# Output_v2_1.net
KiCad netlist of a schematic drawn in EAGLE
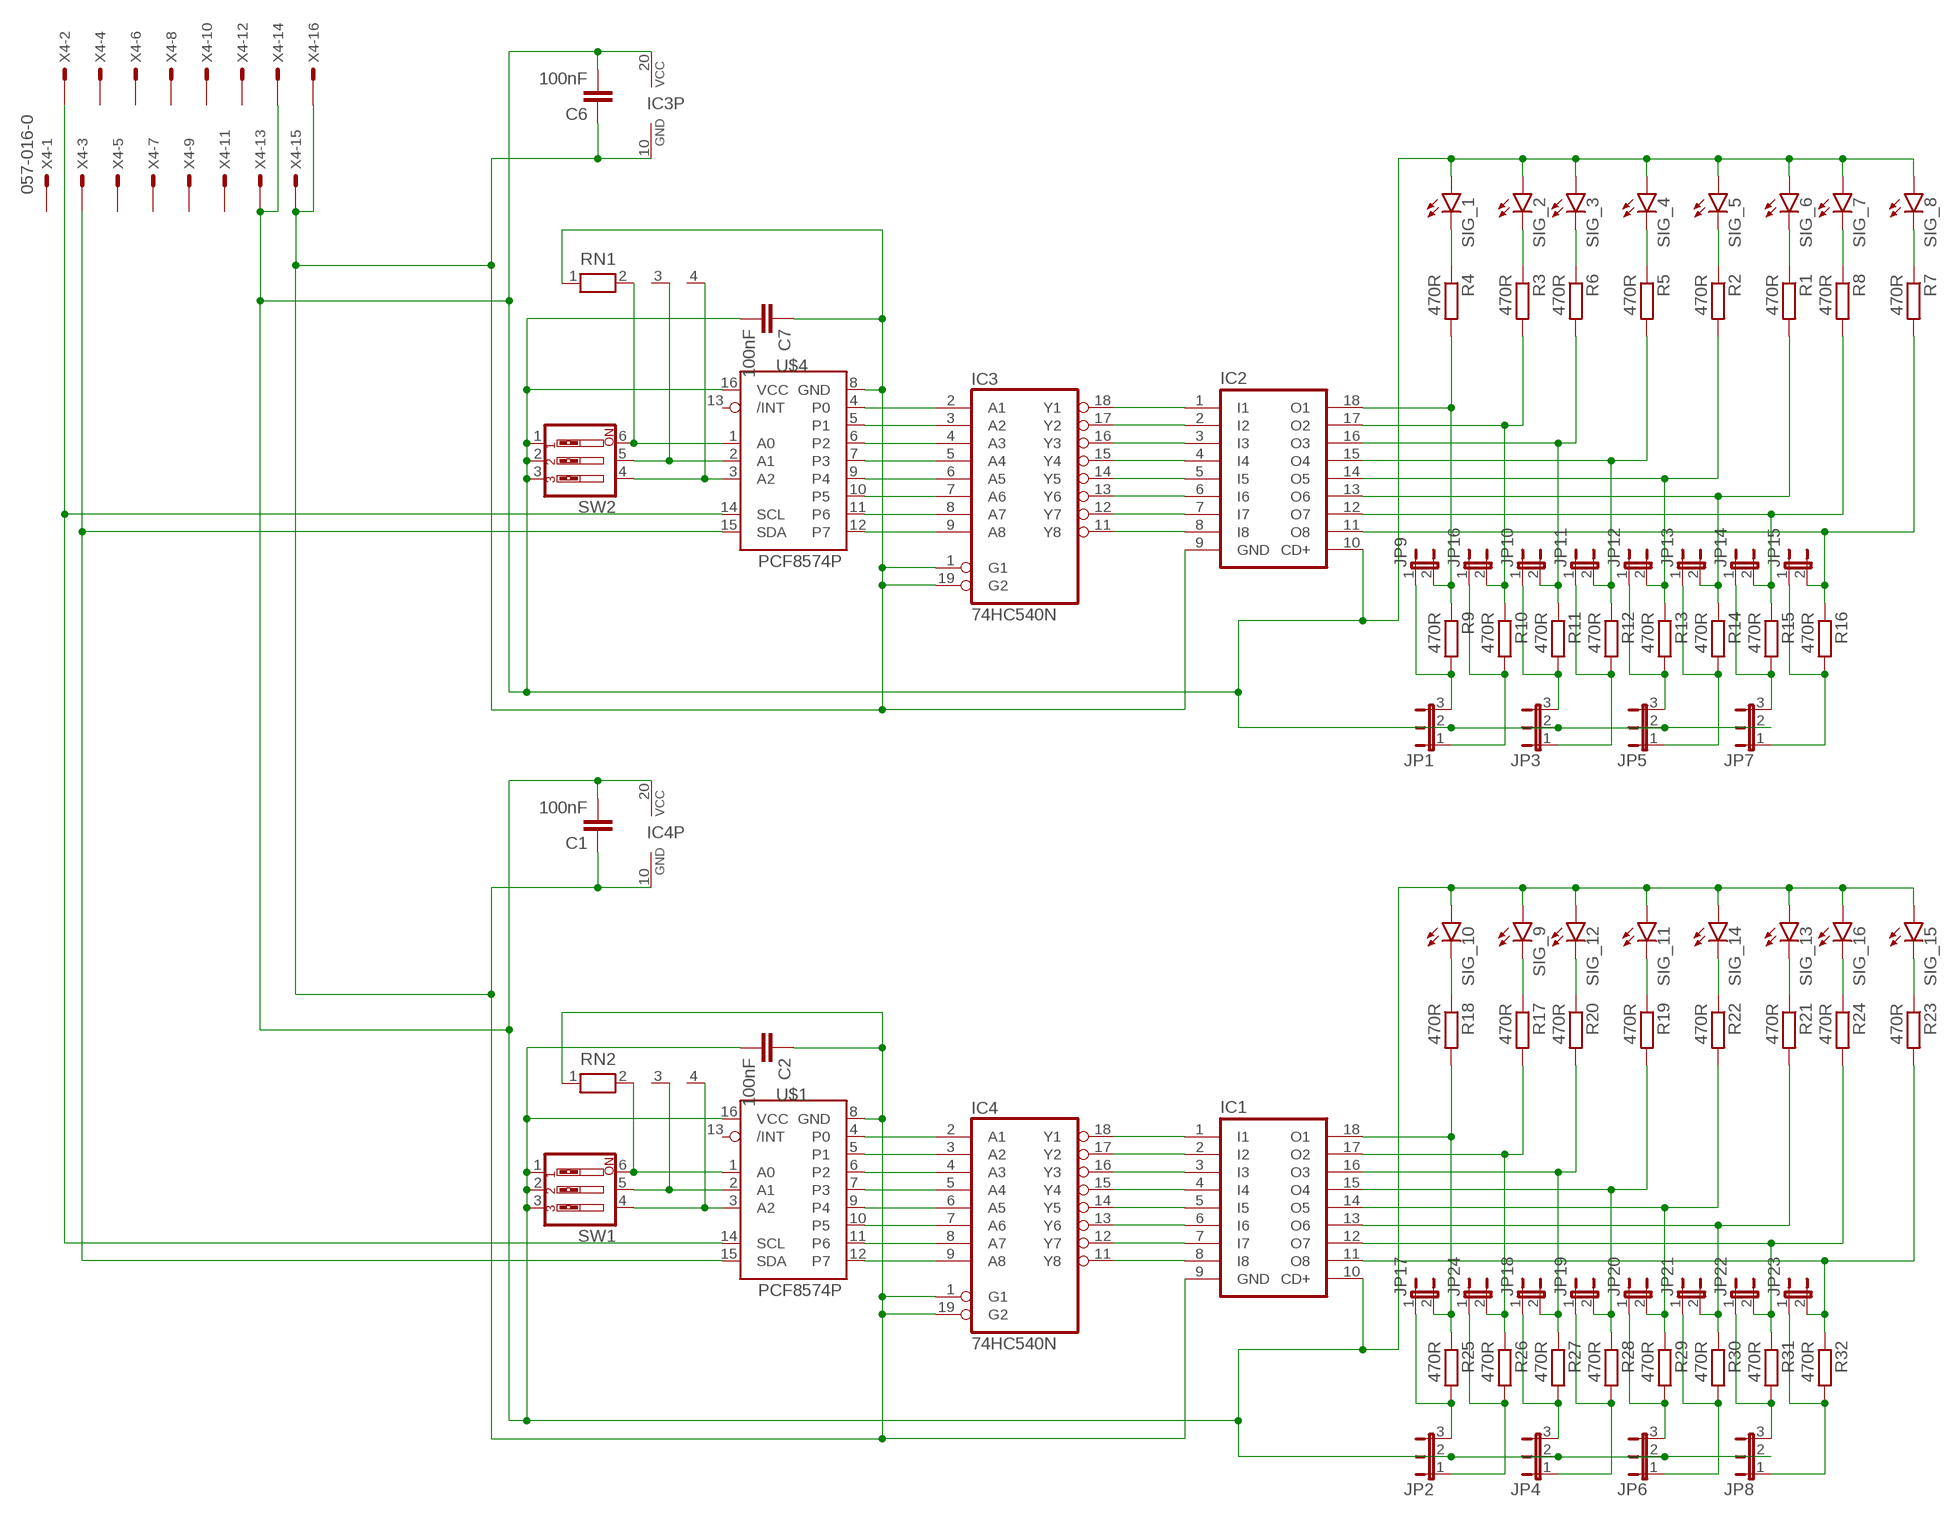
[diagram p0: schematic, sheet 1]

(export (version "E")
  (design (tool "Eeschema 10.0.6"))
  (components
    (comp (ref "C1")
      (value "100nF")
      (footprint "eagle-import:C025-024X044")
      (libsource (lib "eagle-import") (part "C-EU025-024X044"))
    )
    (comp (ref "C2")
      (value "100nF")
      (footprint "eagle-import:C025-024X044")
      (libsource (lib "eagle-import") (part "C-EU025-024X044"))
    )
    (comp (ref "C6")
      (value "100nF")
      (footprint "eagle-import:C025-024X044")
      (libsource (lib "eagle-import") (part "C-EU025-024X044"))
    )
    (comp (ref "C7")
      (value "100nF")
      (footprint "eagle-import:C025-024X044")
      (libsource (lib "eagle-import") (part "C-EU025-024X044"))
    )
    (comp (ref "IC1")
      (value "ULN2803A")
      (footprint "eagle-import:DIL18")
      (libsource (lib "eagle-import") (part "ULN2803A"))
    )
    (comp (ref "IC2")
      (value "ULN2803A")
      (footprint "eagle-import:DIL18")
      (libsource (lib "eagle-import") (part "ULN2803A"))
    )
    (comp (ref "IC3")
      (value "74HC540N")
      (footprint "eagle-import:DIL20")
      (libsource (lib "eagle-import") (part "74540NHC"))
    )
    (comp (ref "IC4")
      (value "74HC540N")
      (footprint "eagle-import:DIL20")
      (libsource (lib "eagle-import") (part "74540NHC"))
    )
    (comp (ref "JP1")
      (value "JP2E")
      (footprint "eagle-import:JP2")
      (libsource (lib "eagle-import") (part "JP2E"))
    )
    (comp (ref "JP2")
      (value "JP2E")
      (footprint "eagle-import:JP2")
      (libsource (lib "eagle-import") (part "JP2E"))
    )
    (comp (ref "JP3")
      (value "JP2E")
      (footprint "eagle-import:JP2")
      (libsource (lib "eagle-import") (part "JP2E"))
    )
    (comp (ref "JP4")
      (value "JP2E")
      (footprint "eagle-import:JP2")
      (libsource (lib "eagle-import") (part "JP2E"))
    )
    (comp (ref "JP5")
      (value "JP2E")
      (footprint "eagle-import:JP2")
      (libsource (lib "eagle-import") (part "JP2E"))
    )
    (comp (ref "JP6")
      (value "JP2E")
      (footprint "eagle-import:JP2")
      (libsource (lib "eagle-import") (part "JP2E"))
    )
    (comp (ref "JP7")
      (value "JP2E")
      (footprint "eagle-import:JP2")
      (libsource (lib "eagle-import") (part "JP2E"))
    )
    (comp (ref "JP8")
      (value "JP2E")
      (footprint "eagle-import:JP2")
      (libsource (lib "eagle-import") (part "JP2E"))
    )
    (comp (ref "JP9")
      (value "JP1E")
      (footprint "eagle-import:JP1")
      (libsource (lib "eagle-import") (part "JP1E"))
    )
    (comp (ref "JP10")
      (value "JP1E")
      (footprint "eagle-import:JP1")
      (libsource (lib "eagle-import") (part "JP1E"))
    )
    (comp (ref "JP11")
      (value "JP1E")
      (footprint "eagle-import:JP1")
      (libsource (lib "eagle-import") (part "JP1E"))
    )
    (comp (ref "JP12")
      (value "JP1E")
      (footprint "eagle-import:JP1")
      (libsource (lib "eagle-import") (part "JP1E"))
    )
    (comp (ref "JP13")
      (value "JP1E")
      (footprint "eagle-import:JP1")
      (libsource (lib "eagle-import") (part "JP1E"))
    )
    (comp (ref "JP14")
      (value "JP1E")
      (footprint "eagle-import:JP1")
      (libsource (lib "eagle-import") (part "JP1E"))
    )
    (comp (ref "JP15")
      (value "JP1E")
      (footprint "eagle-import:JP1")
      (libsource (lib "eagle-import") (part "JP1E"))
    )
    (comp (ref "JP16")
      (value "JP1E")
      (footprint "eagle-import:JP1")
      (libsource (lib "eagle-import") (part "JP1E"))
    )
    (comp (ref "JP17")
      (value "JP1E")
      (footprint "eagle-import:JP1")
      (libsource (lib "eagle-import") (part "JP1E"))
    )
    (comp (ref "JP18")
      (value "JP1E")
      (footprint "eagle-import:JP1")
      (libsource (lib "eagle-import") (part "JP1E"))
    )
    (comp (ref "JP19")
      (value "JP1E")
      (footprint "eagle-import:JP1")
      (libsource (lib "eagle-import") (part "JP1E"))
    )
    (comp (ref "JP20")
      (value "JP1E")
      (footprint "eagle-import:JP1")
      (libsource (lib "eagle-import") (part "JP1E"))
    )
    (comp (ref "JP21")
      (value "JP1E")
      (footprint "eagle-import:JP1")
      (libsource (lib "eagle-import") (part "JP1E"))
    )
    (comp (ref "JP22")
      (value "JP1E")
      (footprint "eagle-import:JP1")
      (libsource (lib "eagle-import") (part "JP1E"))
    )
    (comp (ref "JP23")
      (value "JP1E")
      (footprint "eagle-import:JP1")
      (libsource (lib "eagle-import") (part "JP1E"))
    )
    (comp (ref "JP24")
      (value "JP1E")
      (footprint "eagle-import:JP1")
      (libsource (lib "eagle-import") (part "JP1E"))
    )
    (comp (ref "R1")
      (value "470R")
      (footprint "eagle-import:0309_10")
      (libsource (lib "eagle-import") (part "R-EU_0309/10"))
    )
    (comp (ref "R2")
      (value "470R")
      (footprint "eagle-import:0309_10")
      (libsource (lib "eagle-import") (part "R-EU_0309/10"))
    )
    (comp (ref "R3")
      (value "470R")
      (footprint "eagle-import:0309_10")
      (libsource (lib "eagle-import") (part "R-EU_0309/10"))
    )
    (comp (ref "R4")
      (value "470R")
      (footprint "eagle-import:0309_10")
      (libsource (lib "eagle-import") (part "R-EU_0309/10"))
    )
    (comp (ref "R5")
      (value "470R")
      (footprint "eagle-import:0309_10")
      (libsource (lib "eagle-import") (part "R-EU_0309/10"))
    )
    (comp (ref "R6")
      (value "470R")
      (footprint "eagle-import:0309_10")
      (libsource (lib "eagle-import") (part "R-EU_0309/10"))
    )
    (comp (ref "R7")
      (value "470R")
      (footprint "eagle-import:0309_10")
      (libsource (lib "eagle-import") (part "R-EU_0309/10"))
    )
    (comp (ref "R8")
      (value "470R")
      (footprint "eagle-import:0309_10")
      (libsource (lib "eagle-import") (part "R-EU_0309/10"))
    )
    (comp (ref "R9")
      (value "470R")
      (footprint "eagle-import:0309_10")
      (libsource (lib "eagle-import") (part "R-EU_0309/10"))
    )
    (comp (ref "R10")
      (value "470R")
      (footprint "eagle-import:0309_10")
      (libsource (lib "eagle-import") (part "R-EU_0309/10"))
    )
    (comp (ref "R11")
      (value "470R")
      (footprint "eagle-import:0309_10")
      (libsource (lib "eagle-import") (part "R-EU_0309/10"))
    )
    (comp (ref "R12")
      (value "470R")
      (footprint "eagle-import:0309_10")
      (libsource (lib "eagle-import") (part "R-EU_0309/10"))
    )
    (comp (ref "R13")
      (value "470R")
      (footprint "eagle-import:0309_10")
      (libsource (lib "eagle-import") (part "R-EU_0309/10"))
    )
    (comp (ref "R14")
      (value "470R")
      (footprint "eagle-import:0309_10")
      (libsource (lib "eagle-import") (part "R-EU_0309/10"))
    )
    (comp (ref "R15")
      (value "470R")
      (footprint "eagle-import:0309_10")
      (libsource (lib "eagle-import") (part "R-EU_0309/10"))
    )
    (comp (ref "R16")
      (value "470R")
      (footprint "eagle-import:0309_10")
      (libsource (lib "eagle-import") (part "R-EU_0309/10"))
    )
    (comp (ref "R17")
      (value "470R")
      (footprint "eagle-import:0309_10")
      (libsource (lib "eagle-import") (part "R-EU_0309/10"))
    )
    (comp (ref "R18")
      (value "470R")
      (footprint "eagle-import:0309_10")
      (libsource (lib "eagle-import") (part "R-EU_0309/10"))
    )
    (comp (ref "R19")
      (value "470R")
      (footprint "eagle-import:0309_10")
      (libsource (lib "eagle-import") (part "R-EU_0309/10"))
    )
    (comp (ref "R20")
      (value "470R")
      (footprint "eagle-import:0309_10")
      (libsource (lib "eagle-import") (part "R-EU_0309/10"))
    )
    (comp (ref "R21")
      (value "470R")
      (footprint "eagle-import:0309_10")
      (libsource (lib "eagle-import") (part "R-EU_0309/10"))
    )
    (comp (ref "R22")
      (value "470R")
      (footprint "eagle-import:0309_10")
      (libsource (lib "eagle-import") (part "R-EU_0309/10"))
    )
    (comp (ref "R23")
      (value "470R")
      (footprint "eagle-import:0309_10")
      (libsource (lib "eagle-import") (part "R-EU_0309/10"))
    )
    (comp (ref "R24")
      (value "470R")
      (footprint "eagle-import:0309_10")
      (libsource (lib "eagle-import") (part "R-EU_0309/10"))
    )
    (comp (ref "R25")
      (value "470R")
      (footprint "eagle-import:0309_10")
      (libsource (lib "eagle-import") (part "R-EU_0309/10"))
    )
    (comp (ref "R26")
      (value "470R")
      (footprint "eagle-import:0309_10")
      (libsource (lib "eagle-import") (part "R-EU_0309/10"))
    )
    (comp (ref "R27")
      (value "470R")
      (footprint "eagle-import:0309_10")
      (libsource (lib "eagle-import") (part "R-EU_0309/10"))
    )
    (comp (ref "R28")
      (value "470R")
      (footprint "eagle-import:0309_10")
      (libsource (lib "eagle-import") (part "R-EU_0309/10"))
    )
    (comp (ref "R29")
      (value "470R")
      (footprint "eagle-import:0309_10")
      (libsource (lib "eagle-import") (part "R-EU_0309/10"))
    )
    (comp (ref "R30")
      (value "470R")
      (footprint "eagle-import:0309_10")
      (libsource (lib "eagle-import") (part "R-EU_0309/10"))
    )
    (comp (ref "R31")
      (value "470R")
      (footprint "eagle-import:0309_10")
      (libsource (lib "eagle-import") (part "R-EU_0309/10"))
    )
    (comp (ref "R32")
      (value "470R")
      (footprint "eagle-import:0309_10")
      (libsource (lib "eagle-import") (part "R-EU_0309/10"))
    )
    (comp (ref "RN1")
      (value "RN03")
      (footprint "eagle-import:RN-3")
      (libsource (lib "eagle-import") (part "RN03"))
    )
    (comp (ref "RN2")
      (value "RN03")
      (footprint "eagle-import:RN-3")
      (libsource (lib "eagle-import") (part "RN03"))
    )
    (comp (ref "SIG_1")
      (value "LED3MM")
      (footprint "eagle-import:LED3MM")
      (libsource (lib "eagle-import") (part "LED3MM"))
    )
    (comp (ref "SIG_2")
      (value "LED3MM")
      (footprint "eagle-import:LED3MM")
      (libsource (lib "eagle-import") (part "LED3MM"))
    )
    (comp (ref "SIG_3")
      (value "LED3MM")
      (footprint "eagle-import:LED3MM")
      (libsource (lib "eagle-import") (part "LED3MM"))
    )
    (comp (ref "SIG_4")
      (value "LED3MM")
      (footprint "eagle-import:LED3MM")
      (libsource (lib "eagle-import") (part "LED3MM"))
    )
    (comp (ref "SIG_5")
      (value "LED3MM")
      (footprint "eagle-import:LED3MM")
      (libsource (lib "eagle-import") (part "LED3MM"))
    )
    (comp (ref "SIG_6")
      (value "LED3MM")
      (footprint "eagle-import:LED3MM")
      (libsource (lib "eagle-import") (part "LED3MM"))
    )
    (comp (ref "SIG_7")
      (value "LED3MM")
      (footprint "eagle-import:LED3MM")
      (libsource (lib "eagle-import") (part "LED3MM"))
    )
    (comp (ref "SIG_8")
      (value "LED3MM")
      (footprint "eagle-import:LED3MM")
      (libsource (lib "eagle-import") (part "LED3MM"))
    )
    (comp (ref "SIG_9")
      (value "LED3MM")
      (footprint "eagle-import:LED3MM")
      (libsource (lib "eagle-import") (part "LED3MM"))
    )
    (comp (ref "SIG_10")
      (value "LED3MM")
      (footprint "eagle-import:LED3MM")
      (libsource (lib "eagle-import") (part "LED3MM"))
    )
    (comp (ref "SIG_11")
      (value "LED3MM")
      (footprint "eagle-import:LED3MM")
      (libsource (lib "eagle-import") (part "LED3MM"))
    )
    (comp (ref "SIG_12")
      (value "LED3MM")
      (footprint "eagle-import:LED3MM")
      (libsource (lib "eagle-import") (part "LED3MM"))
    )
    (comp (ref "SIG_13")
      (value "LED3MM")
      (footprint "eagle-import:LED3MM")
      (libsource (lib "eagle-import") (part "LED3MM"))
    )
    (comp (ref "SIG_14")
      (value "LED3MM")
      (footprint "eagle-import:LED3MM")
      (libsource (lib "eagle-import") (part "LED3MM"))
    )
    (comp (ref "SIG_15")
      (value "LED3MM")
      (footprint "eagle-import:LED3MM")
      (libsource (lib "eagle-import") (part "LED3MM"))
    )
    (comp (ref "SIG_16")
      (value "LED3MM")
      (footprint "eagle-import:LED3MM")
      (libsource (lib "eagle-import") (part "LED3MM"))
    )
    (comp (ref "SW1")
      (value "SW_DIP-3")
      (footprint "eagle-import:EDG-03")
      (libsource (lib "eagle-import") (part "SW_DIP-3"))
    )
    (comp (ref "SW2")
      (value "SW_DIP-3")
      (footprint "eagle-import:EDG-03")
      (libsource (lib "eagle-import") (part "SW_DIP-3"))
    )
    (comp (ref "U$1")
      (value "PCF8574P")
      (footprint "eagle-import:DIL16")
      (libsource (lib "eagle-import") (part "PCF8574P"))
    )
    (comp (ref "U$4")
      (value "PCF8574P")
      (footprint "eagle-import:DIL16")
      (libsource (lib "eagle-import") (part "PCF8574P"))
    )
    (comp (ref "X4")
      (value "057-016-0")
      (footprint "eagle-import:057-016-0")
      (libsource (lib "eagle-import") (part "057-016-0"))
    )
  )
  (nets
    (net (code "1") (name "Net-(IC1-CD+)") (class "Default")
      (node (ref "C1") (pin "2") (pinfunction "2_2") (pintype "passive"))
      (node (ref "C2") (pin "2") (pinfunction "2_2") (pintype "passive"))
      (node (ref "C6") (pin "2") (pinfunction "2_2") (pintype "passive"))
      (node (ref "C7") (pin "2") (pinfunction "2_2") (pintype "passive"))
      (node (ref "IC1") (pin "10") (pinfunction "CD+_10") (pintype "passive"))
      (node (ref "IC2") (pin "10") (pinfunction "CD+_10") (pintype "passive"))
      (node (ref "IC3") (pin "20") (pinfunction "VCC_20") (pintype "power_in"))
      (node (ref "IC4") (pin "20") (pinfunction "VCC_20") (pintype "power_in"))
      (node (ref "JP1") (pin "2") (pinfunction "2_2") (pintype "passive"))
      (node (ref "JP2") (pin "2") (pinfunction "2_2") (pintype "passive"))
      (node (ref "JP3") (pin "2") (pinfunction "2_2") (pintype "passive"))
      (node (ref "JP4") (pin "2") (pinfunction "2_2") (pintype "passive"))
      (node (ref "JP5") (pin "2") (pinfunction "2_2") (pintype "passive"))
      (node (ref "JP6") (pin "2") (pinfunction "2_2") (pintype "passive"))
      (node (ref "JP7") (pin "2") (pinfunction "2_2") (pintype "passive"))
      (node (ref "JP8") (pin "2") (pinfunction "2_2") (pintype "passive"))
      (node (ref "SIG_1") (pin "A") (pinfunction "A_A") (pintype "passive"))
      (node (ref "SIG_10") (pin "A") (pinfunction "A_A") (pintype "passive"))
      (node (ref "SIG_11") (pin "A") (pinfunction "A_A") (pintype "passive"))
      (node (ref "SIG_12") (pin "A") (pinfunction "A_A") (pintype "passive"))
      (node (ref "SIG_13") (pin "A") (pinfunction "A_A") (pintype "passive"))
      (node (ref "SIG_14") (pin "A") (pinfunction "A_A") (pintype "passive"))
      (node (ref "SIG_15") (pin "A") (pinfunction "A_A") (pintype "passive"))
      (node (ref "SIG_16") (pin "A") (pinfunction "A_A") (pintype "passive"))
      (node (ref "SIG_2") (pin "A") (pinfunction "A_A") (pintype "passive"))
      (node (ref "SIG_3") (pin "A") (pinfunction "A_A") (pintype "passive"))
      (node (ref "SIG_4") (pin "A") (pinfunction "A_A") (pintype "passive"))
      (node (ref "SIG_5") (pin "A") (pinfunction "A_A") (pintype "passive"))
      (node (ref "SIG_6") (pin "A") (pinfunction "A_A") (pintype "passive"))
      (node (ref "SIG_7") (pin "A") (pinfunction "A_A") (pintype "passive"))
      (node (ref "SIG_8") (pin "A") (pinfunction "A_A") (pintype "passive"))
      (node (ref "SIG_9") (pin "A") (pinfunction "A_A") (pintype "passive"))
      (node (ref "SW1") (pin "1") (pinfunction "1_1") (pintype "passive"))
      (node (ref "SW1") (pin "2") (pinfunction "2_2") (pintype "passive"))
      (node (ref "SW1") (pin "3") (pinfunction "3_3") (pintype "passive"))
      (node (ref "SW2") (pin "1") (pinfunction "1_1") (pintype "passive"))
      (node (ref "SW2") (pin "2") (pinfunction "2_2") (pintype "passive"))
      (node (ref "SW2") (pin "3") (pinfunction "3_3") (pintype "passive"))
      (node (ref "U$1") (pin "16") (pinfunction "VCC_16") (pintype "power_in"))
      (node (ref "U$4") (pin "16") (pinfunction "VCC_16") (pintype "power_in"))
      (node (ref "X4") (pin "13") (pinfunction "S_13") (pintype "passive"))
      (node (ref "X4") (pin "14") (pinfunction "S_14") (pintype "passive"))
    )
    (net (code "2") (name "Net-(IC1-GND)") (class "Default")
      (node (ref "C1") (pin "1") (pinfunction "1_1") (pintype "passive"))
      (node (ref "C2") (pin "1") (pinfunction "1_1") (pintype "passive"))
      (node (ref "C6") (pin "1") (pinfunction "1_1") (pintype "passive"))
      (node (ref "C7") (pin "1") (pinfunction "1_1") (pintype "passive"))
      (node (ref "IC1") (pin "9") (pinfunction "GND_9") (pintype "power_in"))
      (node (ref "IC2") (pin "9") (pinfunction "GND_9") (pintype "power_in"))
      (node (ref "IC3") (pin "1") (pinfunction "G1_1") (pintype "input"))
      (node (ref "IC3") (pin "10") (pinfunction "GND_10") (pintype "power_in"))
      (node (ref "IC3") (pin "19") (pinfunction "G2_19") (pintype "input"))
      (node (ref "IC4") (pin "1") (pinfunction "G1_1") (pintype "input"))
      (node (ref "IC4") (pin "10") (pinfunction "GND_10") (pintype "power_in"))
      (node (ref "IC4") (pin "19") (pinfunction "G2_19") (pintype "input"))
      (node (ref "RN1") (pin "1") (pinfunction "1_1") (pintype "passive"))
      (node (ref "RN2") (pin "1") (pinfunction "1_1") (pintype "passive"))
      (node (ref "U$1") (pin "8") (pinfunction "GND_8") (pintype "power_in"))
      (node (ref "U$4") (pin "8") (pinfunction "GND_8") (pintype "power_in"))
      (node (ref "X4") (pin "15") (pinfunction "S_15") (pintype "passive"))
      (node (ref "X4") (pin "16") (pinfunction "S_16") (pintype "passive"))
    )
    (net (code "3") (name "Net-(IC1-I1)") (class "Default")
      (node (ref "IC1") (pin "1") (pinfunction "I1_1") (pintype "input"))
      (node (ref "IC4") (pin "18") (pinfunction "Y1_18") (pintype "tri_state"))
    )
    (net (code "4") (name "Net-(IC1-I2)") (class "Default")
      (node (ref "IC1") (pin "2") (pinfunction "I2_2") (pintype "input"))
      (node (ref "IC4") (pin "17") (pinfunction "Y2_17") (pintype "tri_state"))
    )
    (net (code "5") (name "Net-(IC1-I3)") (class "Default")
      (node (ref "IC1") (pin "3") (pinfunction "I3_3") (pintype "input"))
      (node (ref "IC4") (pin "16") (pinfunction "Y3_16") (pintype "tri_state"))
    )
    (net (code "6") (name "Net-(IC1-I4)") (class "Default")
      (node (ref "IC1") (pin "4") (pinfunction "I4_4") (pintype "input"))
      (node (ref "IC4") (pin "15") (pinfunction "Y4_15") (pintype "tri_state"))
    )
    (net (code "7") (name "Net-(IC1-I5)") (class "Default")
      (node (ref "IC1") (pin "5") (pinfunction "I5_5") (pintype "input"))
      (node (ref "IC4") (pin "14") (pinfunction "Y5_14") (pintype "tri_state"))
    )
    (net (code "8") (name "Net-(IC1-I6)") (class "Default")
      (node (ref "IC1") (pin "6") (pinfunction "I6_6") (pintype "input"))
      (node (ref "IC4") (pin "13") (pinfunction "Y6_13") (pintype "tri_state"))
    )
    (net (code "9") (name "Net-(IC1-I7)") (class "Default")
      (node (ref "IC1") (pin "7") (pinfunction "I7_7") (pintype "input"))
      (node (ref "IC4") (pin "12") (pinfunction "Y7_12") (pintype "tri_state"))
    )
    (net (code "10") (name "Net-(IC1-I8)") (class "Default")
      (node (ref "IC1") (pin "8") (pinfunction "I8_8") (pintype "input"))
      (node (ref "IC4") (pin "11") (pinfunction "Y8_11") (pintype "tri_state"))
    )
    (net (code "11") (name "Net-(IC1-O1)") (class "Default")
      (node (ref "IC1") (pin "18") (pinfunction "O1_18") (pintype "open_collector"))
      (node (ref "JP17") (pin "2") (pinfunction "2_2") (pintype "passive"))
      (node (ref "R18") (pin "2") (pinfunction "2_2") (pintype "passive"))
      (node (ref "R25") (pin "1") (pinfunction "1_1") (pintype "passive"))
    )
    (net (code "12") (name "Net-(IC1-O2)") (class "Default")
      (node (ref "IC1") (pin "17") (pinfunction "O2_17") (pintype "open_collector"))
      (node (ref "JP24") (pin "2") (pinfunction "2_2") (pintype "passive"))
      (node (ref "R17") (pin "2") (pinfunction "2_2") (pintype "passive"))
      (node (ref "R26") (pin "1") (pinfunction "1_1") (pintype "passive"))
    )
    (net (code "13") (name "Net-(IC1-O3)") (class "Default")
      (node (ref "IC1") (pin "16") (pinfunction "O3_16") (pintype "open_collector"))
      (node (ref "JP18") (pin "2") (pinfunction "2_2") (pintype "passive"))
      (node (ref "R20") (pin "2") (pinfunction "2_2") (pintype "passive"))
      (node (ref "R27") (pin "1") (pinfunction "1_1") (pintype "passive"))
    )
    (net (code "14") (name "Net-(IC1-O4)") (class "Default")
      (node (ref "IC1") (pin "15") (pinfunction "O4_15") (pintype "open_collector"))
      (node (ref "JP19") (pin "2") (pinfunction "2_2") (pintype "passive"))
      (node (ref "R19") (pin "2") (pinfunction "2_2") (pintype "passive"))
      (node (ref "R28") (pin "1") (pinfunction "1_1") (pintype "passive"))
    )
    (net (code "15") (name "Net-(IC1-O5)") (class "Default")
      (node (ref "IC1") (pin "14") (pinfunction "O5_14") (pintype "open_collector"))
      (node (ref "JP20") (pin "2") (pinfunction "2_2") (pintype "passive"))
      (node (ref "R22") (pin "2") (pinfunction "2_2") (pintype "passive"))
      (node (ref "R29") (pin "1") (pinfunction "1_1") (pintype "passive"))
    )
    (net (code "16") (name "Net-(IC1-O6)") (class "Default")
      (node (ref "IC1") (pin "13") (pinfunction "O6_13") (pintype "open_collector"))
      (node (ref "JP21") (pin "2") (pinfunction "2_2") (pintype "passive"))
      (node (ref "R21") (pin "2") (pinfunction "2_2") (pintype "passive"))
      (node (ref "R30") (pin "1") (pinfunction "1_1") (pintype "passive"))
    )
    (net (code "17") (name "Net-(IC1-O7)") (class "Default")
      (node (ref "IC1") (pin "12") (pinfunction "O7_12") (pintype "open_collector"))
      (node (ref "JP22") (pin "2") (pinfunction "2_2") (pintype "passive"))
      (node (ref "R24") (pin "2") (pinfunction "2_2") (pintype "passive"))
      (node (ref "R31") (pin "1") (pinfunction "1_1") (pintype "passive"))
    )
    (net (code "18") (name "Net-(IC1-O8)") (class "Default")
      (node (ref "IC1") (pin "11") (pinfunction "O8_11") (pintype "open_collector"))
      (node (ref "JP23") (pin "2") (pinfunction "2_2") (pintype "passive"))
      (node (ref "R23") (pin "2") (pinfunction "2_2") (pintype "passive"))
      (node (ref "R32") (pin "1") (pinfunction "1_1") (pintype "passive"))
    )
    (net (code "19") (name "Net-(IC2-I1)") (class "Default")
      (node (ref "IC2") (pin "1") (pinfunction "I1_1") (pintype "input"))
      (node (ref "IC3") (pin "18") (pinfunction "Y1_18") (pintype "tri_state"))
    )
    (net (code "20") (name "Net-(IC2-I2)") (class "Default")
      (node (ref "IC2") (pin "2") (pinfunction "I2_2") (pintype "input"))
      (node (ref "IC3") (pin "17") (pinfunction "Y2_17") (pintype "tri_state"))
    )
    (net (code "21") (name "Net-(IC2-I3)") (class "Default")
      (node (ref "IC2") (pin "3") (pinfunction "I3_3") (pintype "input"))
      (node (ref "IC3") (pin "16") (pinfunction "Y3_16") (pintype "tri_state"))
    )
    (net (code "22") (name "Net-(IC2-I4)") (class "Default")
      (node (ref "IC2") (pin "4") (pinfunction "I4_4") (pintype "input"))
      (node (ref "IC3") (pin "15") (pinfunction "Y4_15") (pintype "tri_state"))
    )
    (net (code "23") (name "Net-(IC2-I5)") (class "Default")
      (node (ref "IC2") (pin "5") (pinfunction "I5_5") (pintype "input"))
      (node (ref "IC3") (pin "14") (pinfunction "Y5_14") (pintype "tri_state"))
    )
    (net (code "24") (name "Net-(IC2-I6)") (class "Default")
      (node (ref "IC2") (pin "6") (pinfunction "I6_6") (pintype "input"))
      (node (ref "IC3") (pin "13") (pinfunction "Y6_13") (pintype "tri_state"))
    )
    (net (code "25") (name "Net-(IC2-I7)") (class "Default")
      (node (ref "IC2") (pin "7") (pinfunction "I7_7") (pintype "input"))
      (node (ref "IC3") (pin "12") (pinfunction "Y7_12") (pintype "tri_state"))
    )
    (net (code "26") (name "Net-(IC2-I8)") (class "Default")
      (node (ref "IC2") (pin "8") (pinfunction "I8_8") (pintype "input"))
      (node (ref "IC3") (pin "11") (pinfunction "Y8_11") (pintype "tri_state"))
    )
    (net (code "27") (name "Net-(IC2-O1)") (class "Default")
      (node (ref "IC2") (pin "18") (pinfunction "O1_18") (pintype "open_collector"))
      (node (ref "JP9") (pin "2") (pinfunction "2_2") (pintype "passive"))
      (node (ref "R4") (pin "2") (pinfunction "2_2") (pintype "passive"))
      (node (ref "R9") (pin "1") (pinfunction "1_1") (pintype "passive"))
    )
    (net (code "28") (name "Net-(IC2-O2)") (class "Default")
      (node (ref "IC2") (pin "17") (pinfunction "O2_17") (pintype "open_collector"))
      (node (ref "JP16") (pin "2") (pinfunction "2_2") (pintype "passive"))
      (node (ref "R10") (pin "1") (pinfunction "1_1") (pintype "passive"))
      (node (ref "R3") (pin "2") (pinfunction "2_2") (pintype "passive"))
    )
    (net (code "29") (name "Net-(IC2-O3)") (class "Default")
      (node (ref "IC2") (pin "16") (pinfunction "O3_16") (pintype "open_collector"))
      (node (ref "JP10") (pin "2") (pinfunction "2_2") (pintype "passive"))
      (node (ref "R11") (pin "1") (pinfunction "1_1") (pintype "passive"))
      (node (ref "R6") (pin "2") (pinfunction "2_2") (pintype "passive"))
    )
    (net (code "30") (name "Net-(IC2-O4)") (class "Default")
      (node (ref "IC2") (pin "15") (pinfunction "O4_15") (pintype "open_collector"))
      (node (ref "JP11") (pin "2") (pinfunction "2_2") (pintype "passive"))
      (node (ref "R12") (pin "1") (pinfunction "1_1") (pintype "passive"))
      (node (ref "R5") (pin "2") (pinfunction "2_2") (pintype "passive"))
    )
    (net (code "31") (name "Net-(IC2-O5)") (class "Default")
      (node (ref "IC2") (pin "14") (pinfunction "O5_14") (pintype "open_collector"))
      (node (ref "JP12") (pin "2") (pinfunction "2_2") (pintype "passive"))
      (node (ref "R13") (pin "1") (pinfunction "1_1") (pintype "passive"))
      (node (ref "R2") (pin "2") (pinfunction "2_2") (pintype "passive"))
    )
    (net (code "32") (name "Net-(IC2-O6)") (class "Default")
      (node (ref "IC2") (pin "13") (pinfunction "O6_13") (pintype "open_collector"))
      (node (ref "JP13") (pin "2") (pinfunction "2_2") (pintype "passive"))
      (node (ref "R1") (pin "2") (pinfunction "2_2") (pintype "passive"))
      (node (ref "R14") (pin "1") (pinfunction "1_1") (pintype "passive"))
    )
    (net (code "33") (name "Net-(IC2-O7)") (class "Default")
      (node (ref "IC2") (pin "12") (pinfunction "O7_12") (pintype "open_collector"))
      (node (ref "JP14") (pin "2") (pinfunction "2_2") (pintype "passive"))
      (node (ref "R15") (pin "1") (pinfunction "1_1") (pintype "passive"))
      (node (ref "R8") (pin "2") (pinfunction "2_2") (pintype "passive"))
    )
    (net (code "34") (name "Net-(IC2-O8)") (class "Default")
      (node (ref "IC2") (pin "11") (pinfunction "O8_11") (pintype "open_collector"))
      (node (ref "JP15") (pin "2") (pinfunction "2_2") (pintype "passive"))
      (node (ref "R16") (pin "1") (pinfunction "1_1") (pintype "passive"))
      (node (ref "R7") (pin "2") (pinfunction "2_2") (pintype "passive"))
    )
    (net (code "35") (name "Net-(IC3A-A1)") (class "Default")
      (node (ref "IC3") (pin "2") (pinfunction "A1_2") (pintype "input"))
      (node (ref "U$4") (pin "4") (pinfunction "P0_4") (pintype "bidirectional"))
    )
    (net (code "36") (name "Net-(IC3A-A2)") (class "Default")
      (node (ref "IC3") (pin "3") (pinfunction "A2_3") (pintype "input"))
      (node (ref "U$4") (pin "5") (pinfunction "P1_5") (pintype "bidirectional"))
    )
    (net (code "37") (name "Net-(IC3A-A3)") (class "Default")
      (node (ref "IC3") (pin "4") (pinfunction "A3_4") (pintype "input"))
      (node (ref "U$4") (pin "6") (pinfunction "P2_6") (pintype "bidirectional"))
    )
    (net (code "38") (name "Net-(IC3A-A4)") (class "Default")
      (node (ref "IC3") (pin "5") (pinfunction "A4_5") (pintype "input"))
      (node (ref "U$4") (pin "7") (pinfunction "P3_7") (pintype "bidirectional"))
    )
    (net (code "39") (name "Net-(IC3A-A5)") (class "Default")
      (node (ref "IC3") (pin "6") (pinfunction "A5_6") (pintype "input"))
      (node (ref "U$4") (pin "9") (pinfunction "P4_9") (pintype "bidirectional"))
    )
    (net (code "40") (name "Net-(IC3A-A6)") (class "Default")
      (node (ref "IC3") (pin "7") (pinfunction "A6_7") (pintype "input"))
      (node (ref "U$4") (pin "10") (pinfunction "P5_10") (pintype "bidirectional"))
    )
    (net (code "41") (name "Net-(IC3A-A7)") (class "Default")
      (node (ref "IC3") (pin "8") (pinfunction "A7_8") (pintype "input"))
      (node (ref "U$4") (pin "11") (pinfunction "P6_11") (pintype "bidirectional"))
    )
    (net (code "42") (name "Net-(IC3A-A8)") (class "Default")
      (node (ref "IC3") (pin "9") (pinfunction "A8_9") (pintype "input"))
      (node (ref "U$4") (pin "12") (pinfunction "P7_12") (pintype "bidirectional"))
    )
    (net (code "43") (name "Net-(IC4A-A1)") (class "Default")
      (node (ref "IC4") (pin "2") (pinfunction "A1_2") (pintype "input"))
      (node (ref "U$1") (pin "4") (pinfunction "P0_4") (pintype "bidirectional"))
    )
    (net (code "44") (name "Net-(IC4A-A2)") (class "Default")
      (node (ref "IC4") (pin "3") (pinfunction "A2_3") (pintype "input"))
      (node (ref "U$1") (pin "5") (pinfunction "P1_5") (pintype "bidirectional"))
    )
    (net (code "45") (name "Net-(IC4A-A3)") (class "Default")
      (node (ref "IC4") (pin "4") (pinfunction "A3_4") (pintype "input"))
      (node (ref "U$1") (pin "6") (pinfunction "P2_6") (pintype "bidirectional"))
    )
    (net (code "46") (name "Net-(IC4A-A4)") (class "Default")
      (node (ref "IC4") (pin "5") (pinfunction "A4_5") (pintype "input"))
      (node (ref "U$1") (pin "7") (pinfunction "P3_7") (pintype "bidirectional"))
    )
    (net (code "47") (name "Net-(IC4A-A5)") (class "Default")
      (node (ref "IC4") (pin "6") (pinfunction "A5_6") (pintype "input"))
      (node (ref "U$1") (pin "9") (pinfunction "P4_9") (pintype "bidirectional"))
    )
    (net (code "48") (name "Net-(IC4A-A6)") (class "Default")
      (node (ref "IC4") (pin "7") (pinfunction "A6_7") (pintype "input"))
      (node (ref "U$1") (pin "10") (pinfunction "P5_10") (pintype "bidirectional"))
    )
    (net (code "49") (name "Net-(IC4A-A7)") (class "Default")
      (node (ref "IC4") (pin "8") (pinfunction "A7_8") (pintype "input"))
      (node (ref "U$1") (pin "11") (pinfunction "P6_11") (pintype "bidirectional"))
    )
    (net (code "50") (name "Net-(IC4A-A8)") (class "Default")
      (node (ref "IC4") (pin "9") (pinfunction "A8_9") (pintype "input"))
      (node (ref "U$1") (pin "12") (pinfunction "P7_12") (pintype "bidirectional"))
    )
    (net (code "51") (name "Net-(JP1-Pad1)") (class "Default")
      (node (ref "JP1") (pin "1") (pinfunction "1_1") (pintype "passive"))
      (node (ref "JP16") (pin "1") (pinfunction "1_1") (pintype "passive"))
      (node (ref "R10") (pin "2") (pinfunction "2_2") (pintype "passive"))
    )
    (net (code "52") (name "Net-(JP1-Pad3)") (class "Default")
      (node (ref "JP1") (pin "3") (pinfunction "3_3") (pintype "passive"))
      (node (ref "JP9") (pin "1") (pinfunction "1_1") (pintype "passive"))
      (node (ref "R9") (pin "2") (pinfunction "2_2") (pintype "passive"))
    )
    (net (code "53") (name "Net-(JP2-Pad1)") (class "Default")
      (node (ref "JP2") (pin "1") (pinfunction "1_1") (pintype "passive"))
      (node (ref "JP24") (pin "1") (pinfunction "1_1") (pintype "passive"))
      (node (ref "R26") (pin "2") (pinfunction "2_2") (pintype "passive"))
    )
    (net (code "54") (name "Net-(JP10-Pad1)") (class "Default")
      (node (ref "JP10") (pin "1") (pinfunction "1_1") (pintype "passive"))
      (node (ref "JP3") (pin "3") (pinfunction "3_3") (pintype "passive"))
      (node (ref "R11") (pin "2") (pinfunction "2_2") (pintype "passive"))
    )
    (net (code "55") (name "Net-(JP11-Pad1)") (class "Default")
      (node (ref "JP11") (pin "1") (pinfunction "1_1") (pintype "passive"))
      (node (ref "JP3") (pin "1") (pinfunction "1_1") (pintype "passive"))
      (node (ref "R12") (pin "2") (pinfunction "2_2") (pintype "passive"))
    )
    (net (code "56") (name "Net-(JP12-Pad1)") (class "Default")
      (node (ref "JP12") (pin "1") (pinfunction "1_1") (pintype "passive"))
      (node (ref "JP5") (pin "3") (pinfunction "3_3") (pintype "passive"))
      (node (ref "R13") (pin "2") (pinfunction "2_2") (pintype "passive"))
    )
    (net (code "57") (name "Net-(JP13-Pad1)") (class "Default")
      (node (ref "JP13") (pin "1") (pinfunction "1_1") (pintype "passive"))
      (node (ref "JP5") (pin "1") (pinfunction "1_1") (pintype "passive"))
      (node (ref "R14") (pin "2") (pinfunction "2_2") (pintype "passive"))
    )
    (net (code "58") (name "Net-(JP14-Pad1)") (class "Default")
      (node (ref "JP14") (pin "1") (pinfunction "1_1") (pintype "passive"))
      (node (ref "JP7") (pin "3") (pinfunction "3_3") (pintype "passive"))
      (node (ref "R15") (pin "2") (pinfunction "2_2") (pintype "passive"))
    )
    (net (code "59") (name "Net-(JP15-Pad1)") (class "Default")
      (node (ref "JP15") (pin "1") (pinfunction "1_1") (pintype "passive"))
      (node (ref "JP7") (pin "1") (pinfunction "1_1") (pintype "passive"))
      (node (ref "R16") (pin "2") (pinfunction "2_2") (pintype "passive"))
    )
    (net (code "60") (name "Net-(JP17-Pad1)") (class "Default")
      (node (ref "JP17") (pin "1") (pinfunction "1_1") (pintype "passive"))
      (node (ref "JP2") (pin "3") (pinfunction "3_3") (pintype "passive"))
      (node (ref "R25") (pin "2") (pinfunction "2_2") (pintype "passive"))
    )
    (net (code "61") (name "Net-(JP18-Pad1)") (class "Default")
      (node (ref "JP18") (pin "1") (pinfunction "1_1") (pintype "passive"))
      (node (ref "JP4") (pin "3") (pinfunction "3_3") (pintype "passive"))
      (node (ref "R27") (pin "2") (pinfunction "2_2") (pintype "passive"))
    )
    (net (code "62") (name "Net-(JP19-Pad1)") (class "Default")
      (node (ref "JP19") (pin "1") (pinfunction "1_1") (pintype "passive"))
      (node (ref "JP4") (pin "1") (pinfunction "1_1") (pintype "passive"))
      (node (ref "R28") (pin "2") (pinfunction "2_2") (pintype "passive"))
    )
    (net (code "63") (name "Net-(JP20-Pad1)") (class "Default")
      (node (ref "JP20") (pin "1") (pinfunction "1_1") (pintype "passive"))
      (node (ref "JP6") (pin "3") (pinfunction "3_3") (pintype "passive"))
      (node (ref "R29") (pin "2") (pinfunction "2_2") (pintype "passive"))
    )
    (net (code "64") (name "Net-(JP21-Pad1)") (class "Default")
      (node (ref "JP21") (pin "1") (pinfunction "1_1") (pintype "passive"))
      (node (ref "JP6") (pin "1") (pinfunction "1_1") (pintype "passive"))
      (node (ref "R30") (pin "2") (pinfunction "2_2") (pintype "passive"))
    )
    (net (code "65") (name "Net-(JP22-Pad1)") (class "Default")
      (node (ref "JP22") (pin "1") (pinfunction "1_1") (pintype "passive"))
      (node (ref "JP8") (pin "3") (pinfunction "3_3") (pintype "passive"))
      (node (ref "R31") (pin "2") (pinfunction "2_2") (pintype "passive"))
    )
    (net (code "66") (name "Net-(JP23-Pad1)") (class "Default")
      (node (ref "JP23") (pin "1") (pinfunction "1_1") (pintype "passive"))
      (node (ref "JP8") (pin "1") (pinfunction "1_1") (pintype "passive"))
      (node (ref "R32") (pin "2") (pinfunction "2_2") (pintype "passive"))
    )
    (net (code "67") (name "Net-(SIG_1-C)") (class "Default")
      (node (ref "R4") (pin "1") (pinfunction "1_1") (pintype "passive"))
      (node (ref "SIG_1") (pin "K") (pinfunction "C_K") (pintype "passive"))
    )
    (net (code "68") (name "Net-(SIG_2-C)") (class "Default")
      (node (ref "R3") (pin "1") (pinfunction "1_1") (pintype "passive"))
      (node (ref "SIG_2") (pin "K") (pinfunction "C_K") (pintype "passive"))
    )
    (net (code "69") (name "Net-(SIG_3-C)") (class "Default")
      (node (ref "R6") (pin "1") (pinfunction "1_1") (pintype "passive"))
      (node (ref "SIG_3") (pin "K") (pinfunction "C_K") (pintype "passive"))
    )
    (net (code "70") (name "Net-(SIG_4-C)") (class "Default")
      (node (ref "R5") (pin "1") (pinfunction "1_1") (pintype "passive"))
      (node (ref "SIG_4") (pin "K") (pinfunction "C_K") (pintype "passive"))
    )
    (net (code "71") (name "Net-(SIG_5-C)") (class "Default")
      (node (ref "R2") (pin "1") (pinfunction "1_1") (pintype "passive"))
      (node (ref "SIG_5") (pin "K") (pinfunction "C_K") (pintype "passive"))
    )
    (net (code "72") (name "Net-(SIG_6-C)") (class "Default")
      (node (ref "R1") (pin "1") (pinfunction "1_1") (pintype "passive"))
      (node (ref "SIG_6") (pin "K") (pinfunction "C_K") (pintype "passive"))
    )
    (net (code "73") (name "Net-(SIG_7-C)") (class "Default")
      (node (ref "R8") (pin "1") (pinfunction "1_1") (pintype "passive"))
      (node (ref "SIG_7") (pin "K") (pinfunction "C_K") (pintype "passive"))
    )
    (net (code "74") (name "Net-(SIG_8-C)") (class "Default")
      (node (ref "R7") (pin "1") (pinfunction "1_1") (pintype "passive"))
      (node (ref "SIG_8") (pin "K") (pinfunction "C_K") (pintype "passive"))
    )
    (net (code "75") (name "Net-(SIG_9-C)") (class "Default")
      (node (ref "R17") (pin "1") (pinfunction "1_1") (pintype "passive"))
      (node (ref "SIG_9") (pin "K") (pinfunction "C_K") (pintype "passive"))
    )
    (net (code "76") (name "Net-(SIG_10-C)") (class "Default")
      (node (ref "R18") (pin "1") (pinfunction "1_1") (pintype "passive"))
      (node (ref "SIG_10") (pin "K") (pinfunction "C_K") (pintype "passive"))
    )
    (net (code "77") (name "Net-(SIG_11-C)") (class "Default")
      (node (ref "R19") (pin "1") (pinfunction "1_1") (pintype "passive"))
      (node (ref "SIG_11") (pin "K") (pinfunction "C_K") (pintype "passive"))
    )
    (net (code "78") (name "Net-(SIG_12-C)") (class "Default")
      (node (ref "R20") (pin "1") (pinfunction "1_1") (pintype "passive"))
      (node (ref "SIG_12") (pin "K") (pinfunction "C_K") (pintype "passive"))
    )
    (net (code "79") (name "Net-(SIG_13-C)") (class "Default")
      (node (ref "R21") (pin "1") (pinfunction "1_1") (pintype "passive"))
      (node (ref "SIG_13") (pin "K") (pinfunction "C_K") (pintype "passive"))
    )
    (net (code "80") (name "Net-(SIG_14-C)") (class "Default")
      (node (ref "R22") (pin "1") (pinfunction "1_1") (pintype "passive"))
      (node (ref "SIG_14") (pin "K") (pinfunction "C_K") (pintype "passive"))
    )
    (net (code "81") (name "Net-(SIG_15-C)") (class "Default")
      (node (ref "R23") (pin "1") (pinfunction "1_1") (pintype "passive"))
      (node (ref "SIG_15") (pin "K") (pinfunction "C_K") (pintype "passive"))
    )
    (net (code "82") (name "Net-(SIG_16-C)") (class "Default")
      (node (ref "R24") (pin "1") (pinfunction "1_1") (pintype "passive"))
      (node (ref "SIG_16") (pin "K") (pinfunction "C_K") (pintype "passive"))
    )
    (net (code "83") (name "Net-(U$1-A0)") (class "Default")
      (node (ref "RN2") (pin "2") (pinfunction "2_2") (pintype "passive"))
      (node (ref "SW1") (pin "6") (pinfunction "6_6") (pintype "passive"))
      (node (ref "U$1") (pin "1") (pinfunction "A0_1") (pintype "input"))
    )
    (net (code "84") (name "Net-(U$1-A1)") (class "Default")
      (node (ref "RN2") (pin "3") (pinfunction "3_3") (pintype "passive"))
      (node (ref "SW1") (pin "5") (pinfunction "5_5") (pintype "passive"))
      (node (ref "U$1") (pin "2") (pinfunction "A1_2") (pintype "input"))
    )
    (net (code "85") (name "Net-(U$1-A2)") (class "Default")
      (node (ref "RN2") (pin "4") (pinfunction "4_4") (pintype "passive"))
      (node (ref "SW1") (pin "4") (pinfunction "4_4") (pintype "passive"))
      (node (ref "U$1") (pin "3") (pinfunction "A2_3") (pintype "input"))
    )
    (net (code "86") (name "Net-(U$1-SCL)") (class "Default")
      (node (ref "U$1") (pin "14") (pinfunction "SCL_14") (pintype "input"))
      (node (ref "U$4") (pin "14") (pinfunction "SCL_14") (pintype "input"))
      (node (ref "X4") (pin "2") (pinfunction "S_2") (pintype "passive"))
    )
    (net (code "87") (name "Net-(U$1-SDA)") (class "Default")
      (node (ref "U$1") (pin "15") (pinfunction "SDA_15") (pintype "bidirectional"))
      (node (ref "U$4") (pin "15") (pinfunction "SDA_15") (pintype "bidirectional"))
      (node (ref "X4") (pin "3") (pinfunction "S_3") (pintype "passive"))
    )
    (net (code "88") (name "Net-(U$4-A0)") (class "Default")
      (node (ref "RN1") (pin "2") (pinfunction "2_2") (pintype "passive"))
      (node (ref "SW2") (pin "6") (pinfunction "6_6") (pintype "passive"))
      (node (ref "U$4") (pin "1") (pinfunction "A0_1") (pintype "input"))
    )
    (net (code "89") (name "Net-(U$4-A1)") (class "Default")
      (node (ref "RN1") (pin "3") (pinfunction "3_3") (pintype "passive"))
      (node (ref "SW2") (pin "5") (pinfunction "5_5") (pintype "passive"))
      (node (ref "U$4") (pin "2") (pinfunction "A1_2") (pintype "input"))
    )
    (net (code "90") (name "Net-(U$4-A2)") (class "Default")
      (node (ref "RN1") (pin "4") (pinfunction "4_4") (pintype "passive"))
      (node (ref "SW2") (pin "4") (pinfunction "4_4") (pintype "passive"))
      (node (ref "U$4") (pin "3") (pinfunction "A2_3") (pintype "input"))
    )
    (net (code "91") (name "unconnected-(U$1-{slash}INT-Pad13)") (class "Default")
      (node (ref "U$1") (pin "13") (pinfunction "/INT_13") (pintype "output"))
    )
    (net (code "92") (name "unconnected-(U$4-{slash}INT-Pad13)") (class "Default")
      (node (ref "U$4") (pin "13") (pinfunction "/INT_13") (pintype "output"))
    )
    (net (code "93") (name "unconnected-(X4A-S-Pad1)") (class "Default")
      (node (ref "X4") (pin "1") (pinfunction "S_1") (pintype "passive"))
    )
    (net (code "94") (name "unconnected-(X4B-S-Pad10)") (class "Default")
      (node (ref "X4") (pin "10") (pinfunction "S_10") (pintype "passive"))
    )
    (net (code "95") (name "unconnected-(X4C-S-Pad11)") (class "Default")
      (node (ref "X4") (pin "11") (pinfunction "S_11") (pintype "passive"))
    )
    (net (code "96") (name "unconnected-(X4D-S-Pad12)") (class "Default")
      (node (ref "X4") (pin "12") (pinfunction "S_12") (pintype "passive"))
    )
    (net (code "97") (name "unconnected-(X4K-S-Pad4)") (class "Default")
      (node (ref "X4") (pin "4") (pinfunction "S_4") (pintype "passive"))
    )
    (net (code "98") (name "unconnected-(X4L-S-Pad5)") (class "Default")
      (node (ref "X4") (pin "5") (pinfunction "S_5") (pintype "passive"))
    )
    (net (code "99") (name "unconnected-(X4M-S-Pad6)") (class "Default")
      (node (ref "X4") (pin "6") (pinfunction "S_6") (pintype "passive"))
    )
    (net (code "100") (name "unconnected-(X4N-S-Pad7)") (class "Default")
      (node (ref "X4") (pin "7") (pinfunction "S_7") (pintype "passive"))
    )
    (net (code "101") (name "unconnected-(X4O-S-Pad8)") (class "Default")
      (node (ref "X4") (pin "8") (pinfunction "S_8") (pintype "passive"))
    )
    (net (code "102") (name "unconnected-(X4P-S-Pad9)") (class "Default")
      (node (ref "X4") (pin "9") (pinfunction "S_9") (pintype "passive"))
    )
  )
)
